# Mircod_TEST_LIST_3.net
KiCad netlist of a schematic drawn in Altium Designer
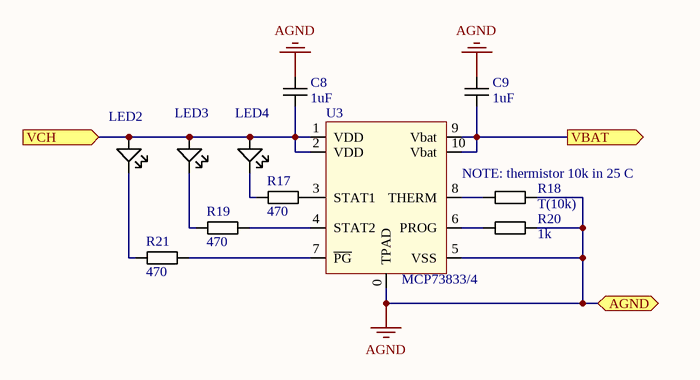
[diagram p0: Mircod_TEST_LIST_3.SchDoc]

(export (version "E")
  (design (tool "Eeschema 10.0.6"))
  (components
    (comp (ref "C8")
      (value "1uF")
      (footprint "MIRCOD:CSMD_0603")
      (description "CAPACITOR")
      (libsource (lib "MIRCOD") (part "C_SMD"))
    )
    (comp (ref "C9")
      (value "1uF")
      (footprint "MIRCOD:CSMD_0603")
      (description "CAPACITOR")
      (libsource (lib "MIRCOD") (part "C_SMD"))
    )
    (comp (ref "LED2") (value "LED") (footprint "MIRCOD:GDSMD_0603") (libsource (lib "MIRCOD") (part "LED")))
    (comp (ref "LED3") (value "LED") (footprint "MIRCOD:GDSMD_0603") (libsource (lib "MIRCOD") (part "LED")))
    (comp (ref "LED4") (value "LED") (footprint "MIRCOD:BDSMD_0603") (libsource (lib "MIRCOD") (part "LED")))
    (comp (ref "R17")
      (value "470")
      (footprint "MIRCOD:SMD_0603")
      (description "RESISTOR")
      (libsource (lib "MIRCOD") (part "R_SMD"))
    )
    (comp (ref "R18")
      (value "T(10k)")
      (footprint "MIRCOD:SMD_0603")
      (description "RESISTOR")
      (libsource (lib "MIRCOD") (part "R_SMD"))
    )
    (comp (ref "R19")
      (value "470")
      (footprint "MIRCOD:SMD_0603")
      (description "RESISTOR")
      (libsource (lib "MIRCOD") (part "R_SMD"))
    )
    (comp (ref "R20")
      (value "1k")
      (footprint "MIRCOD:SMD_0603")
      (description "RESISTOR")
      (libsource (lib "MIRCOD") (part "R_SMD"))
    )
    (comp (ref "R21")
      (value "470")
      (footprint "MIRCOD:SMD_0603")
      (description "RESISTOR")
      (libsource (lib "MIRCOD") (part "R_SMD"))
    )
    (comp (ref "U3")
      (value "MCP73833/4")
      (footprint "MIRCOD:10-Lead, 3mm x 3mm DFN")
      (description "Stand-Alone Linear Li-Ion / Li-Polymer Charge  Management Controller")
      (libsource (lib "MIRCOD") (part "MCP73833/4"))
    )
  )
  (nets
    (net (code "1") (name "/VBAT") (class "Default")
      (node (ref "C9") (pin "2") (pinfunction "2_2") (pintype "passive"))
      (node (ref "U3") (pin "10") (pinfunction "Vbat_10") (pintype "passive"))
      (node (ref "U3") (pin "9") (pinfunction "Vbat_9") (pintype "passive"))
    )
    (net (code "2") (name "/VCH") (class "Default")
      (node (ref "C8") (pin "2") (pinfunction "2_2") (pintype "passive"))
      (node (ref "LED2") (pin "1") (pinfunction "1_1") (pintype "passive"))
      (node (ref "LED3") (pin "1") (pinfunction "1_1") (pintype "passive"))
      (node (ref "LED4") (pin "1") (pinfunction "1_1") (pintype "passive"))
      (node (ref "U3") (pin "1") (pinfunction "VDD_1") (pintype "passive"))
      (node (ref "U3") (pin "2") (pinfunction "VDD_2") (pintype "passive"))
    )
    (net (code "3") (name "AGND") (class "Default")
      (node (ref "C8") (pin "1") (pinfunction "1_1") (pintype "passive"))
      (node (ref "C9") (pin "1") (pinfunction "1_1") (pintype "passive"))
      (node (ref "R18") (pin "1") (pinfunction "1_1") (pintype "passive"))
      (node (ref "R20") (pin "1") (pinfunction "1_1") (pintype "passive"))
      (node (ref "U3") (pin "0") (pinfunction "TPAD_0") (pintype "passive"))
      (node (ref "U3") (pin "5") (pinfunction "VSS_5") (pintype "passive"))
    )
    (net (code "4") (name "Net-(LED2-Pad2)") (class "Default")
      (node (ref "LED2") (pin "2") (pinfunction "2_2") (pintype "passive"))
      (node (ref "R21") (pin "2") (pinfunction "2_2") (pintype "passive"))
    )
    (net (code "5") (name "Net-(LED3-Pad2)") (class "Default")
      (node (ref "LED3") (pin "2") (pinfunction "2_2") (pintype "passive"))
      (node (ref "R19") (pin "2") (pinfunction "2_2") (pintype "passive"))
    )
    (net (code "6") (name "Net-(LED4-Pad2)") (class "Default")
      (node (ref "LED4") (pin "2") (pinfunction "2_2") (pintype "passive"))
      (node (ref "R17") (pin "2") (pinfunction "2_2") (pintype "passive"))
    )
    (net (code "7") (name "Net-(U3-PROG)") (class "Default")
      (node (ref "R20") (pin "2") (pinfunction "2_2") (pintype "passive"))
      (node (ref "U3") (pin "6") (pinfunction "PROG_6") (pintype "passive"))
    )
    (net (code "8") (name "Net-(U3-STAT1)") (class "Default")
      (node (ref "R17") (pin "1") (pinfunction "1_1") (pintype "passive"))
      (node (ref "U3") (pin "3") (pinfunction "STAT1_3") (pintype "passive"))
    )
    (net (code "9") (name "Net-(U3-STAT2)") (class "Default")
      (node (ref "R19") (pin "1") (pinfunction "1_1") (pintype "passive"))
      (node (ref "U3") (pin "4") (pinfunction "STAT2_4") (pintype "passive"))
    )
    (net (code "10") (name "Net-(U3-THERM)") (class "Default")
      (node (ref "R18") (pin "2") (pinfunction "2_2") (pintype "passive"))
      (node (ref "U3") (pin "8") (pinfunction "THERM_8") (pintype "passive"))
    )
    (net (code "11") (name "Net-(U3-~{PG})") (class "Default")
      (node (ref "R21") (pin "1") (pinfunction "1_1") (pintype "passive"))
      (node (ref "U3") (pin "7") (pinfunction "~{PG}_7") (pintype "passive"))
    )
  )
)
